# Fuente_Alimentaci_n.net
KiCad netlist of a schematic drawn in EAGLE
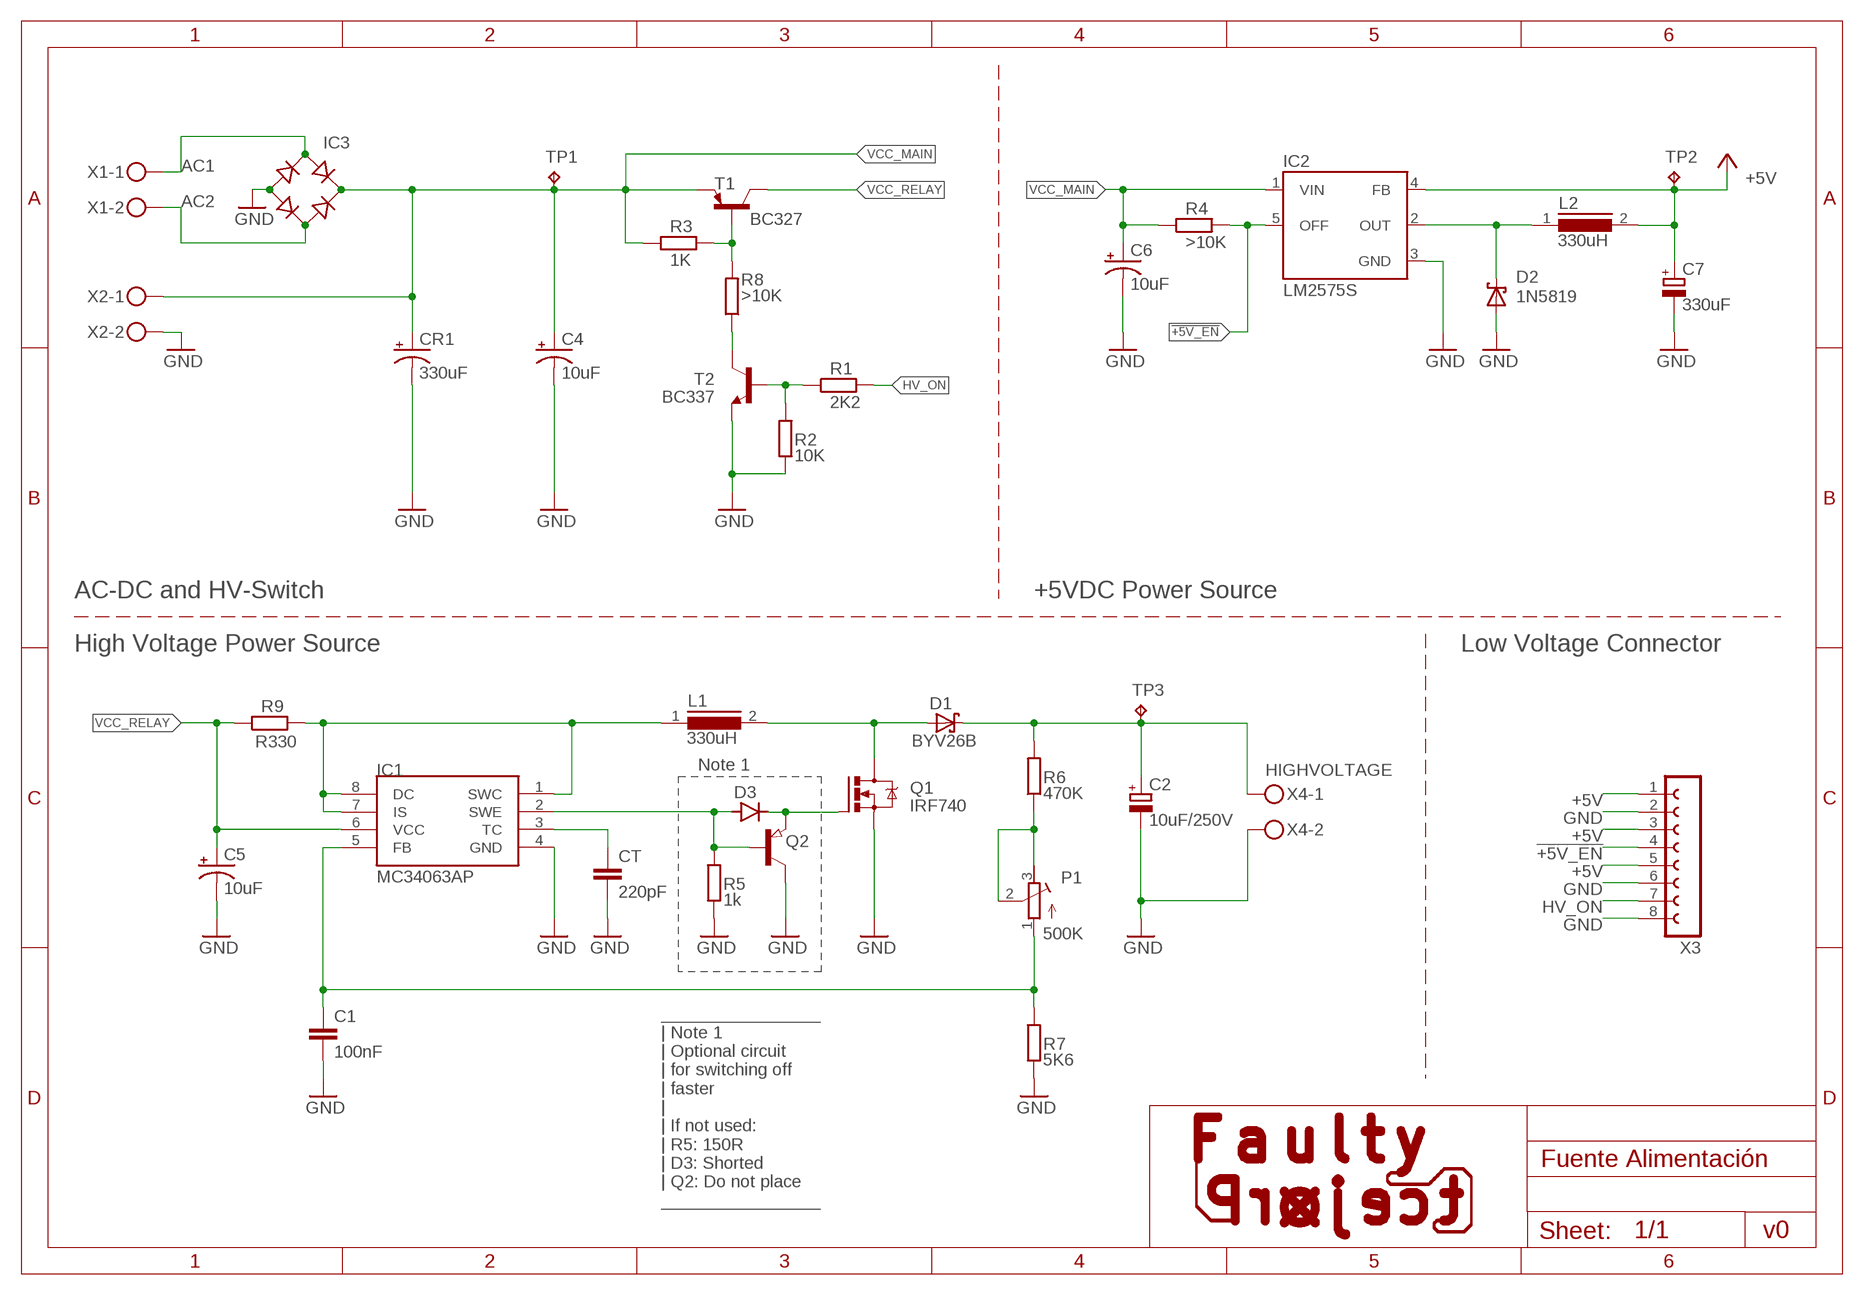
[diagram p0: schematic, sheet 1]

(export (version "E")
  (design (tool "Eeschema 10.0.6"))
  (components
    (comp (ref "C1")
      (value "100nF")
      (footprint "eagle-import:C1808")
      (libsource (lib "eagle-import") (part "C-EUC1808"))
    )
    (comp (ref "C2")
      (value "10uF/250V")
      (footprint "eagle-import:E5-13")
      (libsource (lib "eagle-import") (part "CPOL-EUE5-13"))
    )
    (comp (ref "C4")
      (value "10uF")
      (footprint "eagle-import:085CS_1AR")
      (libsource (lib "eagle-import") (part "CPOL-US085CS-1AR"))
    )
    (comp (ref "C5")
      (value "10uF")
      (footprint "eagle-import:085CS_1AR")
      (libsource (lib "eagle-import") (part "CPOL-US085CS-1AR"))
    )
    (comp (ref "C6")
      (value "10uF")
      (footprint "eagle-import:085CS_1AR")
      (libsource (lib "eagle-import") (part "CPOL-US085CS-1AR"))
    )
    (comp (ref "C7")
      (value "330uF")
      (footprint "eagle-import:E5-10,5")
      (libsource (lib "eagle-import") (part "CPOL-EUE5-10.5"))
    )
    (comp (ref "CR1")
      (value "330uF")
      (footprint "eagle-import:E5-13")
      (libsource (lib "eagle-import") (part "CPOL-USE5-13"))
    )
    (comp (ref "CT")
      (value "220pF")
      (footprint "eagle-import:C025-024X044")
      (libsource (lib "eagle-import") (part "C-EU025-024X044"))
    )
    (comp (ref "D1")
      (value "BYV26B")
      (footprint "eagle-import:DO41-7.6")
      (libsource (lib "eagle-import") (part "1N5817-B"))
    )
    (comp (ref "D2")
      (value "1N5819")
      (footprint "eagle-import:DO41-7.6")
      (libsource (lib "eagle-import") (part "1N5819-T"))
    )
    (comp (ref "D3")
      (value "MBR0520LT")
      (footprint "eagle-import:SOD123")
      (libsource (lib "eagle-import") (part "MBR0520LT"))
    )
    (comp (ref "IC1")
      (value "MC34063AP")
      (footprint "eagle-import:DIL08")
      (libsource (lib "eagle-import") (part "MC34063AP"))
    )
    (comp (ref "IC2")
      (value "LM2575S")
      (footprint "eagle-import:TO263-5")
      (libsource (lib "eagle-import") (part "LM2575S"))
    )
    (comp (ref "IC3")
      (value "B-DIL")
      (footprint "eagle-import:B-DIL")
      (libsource (lib "eagle-import") (part "B-DIL"))
    )
    (comp (ref "L1")
      (value "330uH")
      (footprint "eagle-import:DR125")
      (libsource (lib "eagle-import") (part "DR125"))
    )
    (comp (ref "L2")
      (value "330uH")
      (footprint "eagle-import:DR125")
      (libsource (lib "eagle-import") (part "DR125"))
    )
    (comp (ref "P1")
      (value "500K")
      (footprint "eagle-import:RTRIM64W")
      (libsource (lib "eagle-import") (part "R-TRIMM64W"))
    )
    (comp (ref "Q1")
      (value "IRF740")
      (footprint "eagle-import:TO220BV")
      (libsource (lib "eagle-import") (part "IRF740"))
    )
    (comp (ref "Q2")
      (value "PNP-TRANSISTOR_SOT23")
      (footprint "eagle-import:SOT23")
      (libsource (lib "eagle-import") (part "PNP-TRANSISTOR_SOT23"))
    )
    (comp (ref "R1")
      (value "2K2")
      (footprint "eagle-import:0207_2V")
      (libsource (lib "eagle-import") (part "R-EU_0207/2V"))
    )
    (comp (ref "R2")
      (value "10K")
      (footprint "eagle-import:0207_2V")
      (libsource (lib "eagle-import") (part "R-EU_0207/2V"))
    )
    (comp (ref "R3")
      (value "1K")
      (footprint "eagle-import:0204_5")
      (libsource (lib "eagle-import") (part "R-EU_0204/5"))
    )
    (comp (ref "R4")
      (value ">10K")
      (footprint "eagle-import:0207_2V")
      (libsource (lib "eagle-import") (part "R-EU_0207/2V"))
    )
    (comp (ref "R5")
      (value "1k")
      (footprint "eagle-import:0204V")
      (libsource (lib "eagle-import") (part "R-EU_0204/2V"))
    )
    (comp (ref "R6")
      (value "470K")
      (footprint "eagle-import:0204_7")
      (libsource (lib "eagle-import") (part "R-EU_0204/7"))
    )
    (comp (ref "R7")
      (value "5K6")
      (footprint "eagle-import:0204V")
      (libsource (lib "eagle-import") (part "R-EU_0204/2V"))
    )
    (comp (ref "R8")
      (value ">10K")
      (footprint "eagle-import:0204V")
      (libsource (lib "eagle-import") (part "R-EU_0204/2V"))
    )
    (comp (ref "R9")
      (value "R330")
      (footprint "eagle-import:0204V")
      (libsource (lib "eagle-import") (part "R-EU_0204/2V"))
    )
    (comp (ref "T1")
      (value "BC327")
      (footprint "eagle-import:TO92")
      (libsource (lib "eagle-import") (part "BC327"))
    )
    (comp (ref "T2")
      (value "BC337")
      (footprint "eagle-import:TO92")
      (libsource (lib "eagle-import") (part "BC337"))
    )
    (comp (ref "TP1")
      (value "TPB1,27")
      (footprint "eagle-import:B1,27")
      (libsource (lib "eagle-import") (part "TPB1,27"))
    )
    (comp (ref "TP2")
      (value "TPB1,27")
      (footprint "eagle-import:B1,27")
      (libsource (lib "eagle-import") (part "TPB1,27"))
    )
    (comp (ref "TP3")
      (value "TPB1,27")
      (footprint "eagle-import:B1,27")
      (libsource (lib "eagle-import") (part "TPB1,27"))
    )
    (comp (ref "X1")
      (value "MKDSN1,5/2-5,08")
      (footprint "eagle-import:MKDSN1,5_2-5,08")
      (libsource (lib "eagle-import") (part "MKDSN1,5/2-5,08"))
    )
    (comp (ref "X2")
      (value "MKDSN1,5/2-5,08")
      (footprint "eagle-import:MKDSN1,5_2-5,08")
      (libsource (lib "eagle-import") (part "MKDSN1,5/2-5,08"))
    )
    (comp (ref "X3")
      (value "FE08W")
      (footprint "eagle-import:FE08W")
      (libsource (lib "eagle-import") (part "FE08W"))
    )
    (comp (ref "X4")
      (value "MKDSN1,5/2-5,08")
      (footprint "eagle-import:MKDSN1,5_2-5,08")
      (libsource (lib "eagle-import") (part "MKDSN1,5/2-5,08"))
    )
  )
  (nets
    (net (code "1") (name "+5V") (class "Default")
      (node (ref "C7") (pin "+") (pinfunction "+_+") (pintype "passive"))
      (node (ref "IC2") (pin "4") (pinfunction "FB_4") (pintype "input"))
      (node (ref "L2") (pin "2") (pinfunction "2_2") (pintype "passive"))
      (node (ref "TP2") (pin "TP") (pinfunction "TP_TP") (pintype "input"))
      (node (ref "X3") (pin "1") (pinfunction "1_1") (pintype "passive"))
      (node (ref "X3") (pin "3") (pinfunction "3_3") (pintype "passive"))
      (node (ref "X3") (pin "5") (pinfunction "5_5") (pintype "passive"))
    )
    (net (code "2") (name "/AC1") (class "Default")
      (node (ref "IC3") (pin "AC2") (pinfunction "AC2_AC2") (pintype "passive"))
      (node (ref "X1") (pin "1") (pinfunction "KL_1") (pintype "passive"))
    )
    (net (code "3") (name "/AC2") (class "Default")
      (node (ref "IC3") (pin "AC1") (pinfunction "AC1_AC1") (pintype "passive"))
      (node (ref "X1") (pin "2") (pinfunction "KL_2") (pintype "passive"))
    )
    (net (code "4") (name "/HIGHVOLTAGE") (class "Default")
      (node (ref "C2") (pin "+") (pinfunction "+_+") (pintype "passive"))
      (node (ref "D1") (pin "C") (pinfunction "C_C") (pintype "passive"))
      (node (ref "R6") (pin "2") (pinfunction "2_2") (pintype "passive"))
      (node (ref "TP3") (pin "TP") (pinfunction "TP_TP") (pintype "input"))
      (node (ref "X4") (pin "1") (pinfunction "KL_1") (pintype "passive"))
    )
    (net (code "5") (name "/~{+5V_EN}") (class "Default")
      (node (ref "IC2") (pin "5") (pinfunction "OFF_5") (pintype "input"))
      (node (ref "R4") (pin "2") (pinfunction "2_2") (pintype "passive"))
      (node (ref "X3") (pin "4") (pinfunction "4_4") (pintype "passive"))
    )
    (net (code "6") (name "GND") (class "Default")
      (node (ref "C1") (pin "2") (pinfunction "2_2") (pintype "passive"))
      (node (ref "C2") (pin "-") (pinfunction "-_-") (pintype "passive"))
      (node (ref "C4") (pin "-") (pinfunction "-_-") (pintype "passive"))
      (node (ref "C5") (pin "-") (pinfunction "-_-") (pintype "passive"))
      (node (ref "C6") (pin "-") (pinfunction "-_-") (pintype "passive"))
      (node (ref "C7") (pin "-") (pinfunction "-_-") (pintype "passive"))
      (node (ref "CR1") (pin "-") (pinfunction "-_-") (pintype "passive"))
      (node (ref "CT") (pin "2") (pinfunction "2_2") (pintype "passive"))
      (node (ref "D2") (pin "A") (pinfunction "A_A") (pintype "passive"))
      (node (ref "IC1") (pin "4") (pinfunction "GND_4") (pintype "passive"))
      (node (ref "IC2") (pin "3") (pinfunction "GND_3") (pintype "power_in"))
      (node (ref "IC3") (pin "-") (pinfunction "-_-") (pintype "passive"))
      (node (ref "Q1") (pin "S") (pinfunction "S_S") (pintype "passive"))
      (node (ref "Q2") (pin "3") (pinfunction "C_3") (pintype "passive"))
      (node (ref "R2") (pin "1") (pinfunction "1_1") (pintype "passive"))
      (node (ref "R5") (pin "1") (pinfunction "1_1") (pintype "passive"))
      (node (ref "R7") (pin "1") (pinfunction "1_1") (pintype "passive"))
      (node (ref "T2") (pin "1") (pinfunction "E_1") (pintype "passive"))
      (node (ref "X2") (pin "2") (pinfunction "KL_2") (pintype "passive"))
      (node (ref "X3") (pin "2") (pinfunction "2_2") (pintype "passive"))
      (node (ref "X3") (pin "6") (pinfunction "6_6") (pintype "passive"))
      (node (ref "X3") (pin "8") (pinfunction "8_8") (pintype "passive"))
      (node (ref "X4") (pin "2") (pinfunction "KL_2") (pintype "passive"))
    )
    (net (code "7") (name "HV_ON") (class "Default")
      (node (ref "R1") (pin "2") (pinfunction "2_2") (pintype "passive"))
      (node (ref "X3") (pin "7") (pinfunction "7_7") (pintype "passive"))
    )
    (net (code "8") (name "Net-(D1-PadA)") (class "Default")
      (node (ref "D1") (pin "A") (pinfunction "A_A") (pintype "passive"))
      (node (ref "L1") (pin "2") (pinfunction "2_2") (pintype "passive"))
      (node (ref "Q1") (pin "D") (pinfunction "D_D") (pintype "passive"))
    )
    (net (code "9") (name "Net-(IC1-DC)") (class "Default")
      (node (ref "IC1") (pin "1") (pinfunction "SWC_1") (pintype "passive"))
      (node (ref "IC1") (pin "7") (pinfunction "IS_7") (pintype "passive"))
      (node (ref "IC1") (pin "8") (pinfunction "DC_8") (pintype "passive"))
      (node (ref "L1") (pin "1") (pinfunction "1_1") (pintype "passive"))
      (node (ref "R9") (pin "2") (pinfunction "2_2") (pintype "passive"))
    )
    (net (code "10") (name "Net-(IC1-FB)") (class "Default")
      (node (ref "C1") (pin "1") (pinfunction "1_1") (pintype "passive"))
      (node (ref "IC1") (pin "5") (pinfunction "FB_5") (pintype "passive"))
      (node (ref "P1") (pin "1") (pinfunction "A_1") (pintype "passive"))
      (node (ref "R7") (pin "2") (pinfunction "2_2") (pintype "passive"))
    )
    (net (code "11") (name "Net-(IC1-SWE)") (class "Default")
      (node (ref "D3") (pin "A") (pinfunction "A_A") (pintype "passive"))
      (node (ref "IC1") (pin "2") (pinfunction "SWE_2") (pintype "passive"))
      (node (ref "Q2") (pin "1") (pinfunction "B_1") (pintype "passive"))
      (node (ref "R5") (pin "2") (pinfunction "2_2") (pintype "passive"))
    )
    (net (code "12") (name "Net-(IC1-TC)") (class "Default")
      (node (ref "CT") (pin "1") (pinfunction "1_1") (pintype "passive"))
      (node (ref "IC1") (pin "3") (pinfunction "TC_3") (pintype "passive"))
    )
    (net (code "13") (name "Net-(IC2-OUT)") (class "Default")
      (node (ref "D2") (pin "C") (pinfunction "C_C") (pintype "passive"))
      (node (ref "IC2") (pin "2") (pinfunction "OUT_2") (pintype "output"))
      (node (ref "L2") (pin "1") (pinfunction "1_1") (pintype "passive"))
    )
    (net (code "14") (name "Net-(P1-E)") (class "Default")
      (node (ref "P1") (pin "2") (pinfunction "S_2") (pintype "passive"))
      (node (ref "P1") (pin "3") (pinfunction "E_3") (pintype "passive"))
      (node (ref "R6") (pin "1") (pinfunction "1_1") (pintype "passive"))
    )
    (net (code "15") (name "Net-(Q2-E)") (class "Default")
      (node (ref "D3") (pin "C") (pinfunction "C_C") (pintype "passive"))
      (node (ref "Q1") (pin "G") (pinfunction "G_G") (pintype "passive"))
      (node (ref "Q2") (pin "2") (pinfunction "E_2") (pintype "passive"))
    )
    (net (code "16") (name "Net-(T1-B)") (class "Default")
      (node (ref "R3") (pin "2") (pinfunction "2_2") (pintype "passive"))
      (node (ref "R8") (pin "2") (pinfunction "2_2") (pintype "passive"))
      (node (ref "T1") (pin "2") (pinfunction "B_2") (pintype "passive"))
    )
    (net (code "17") (name "Net-(T2-B)") (class "Default")
      (node (ref "R1") (pin "1") (pinfunction "1_1") (pintype "passive"))
      (node (ref "R2") (pin "2") (pinfunction "2_2") (pintype "passive"))
      (node (ref "T2") (pin "2") (pinfunction "B_2") (pintype "passive"))
    )
    (net (code "18") (name "Net-(T2-C)") (class "Default")
      (node (ref "R8") (pin "1") (pinfunction "1_1") (pintype "passive"))
      (node (ref "T2") (pin "3") (pinfunction "C_3") (pintype "passive"))
    )
    (net (code "19") (name "VCC_MAIN") (class "Default")
      (node (ref "C4") (pin "+") (pinfunction "+_+") (pintype "passive"))
      (node (ref "C6") (pin "+") (pinfunction "+_+") (pintype "passive"))
      (node (ref "CR1") (pin "+") (pinfunction "+_+") (pintype "passive"))
      (node (ref "IC2") (pin "1") (pinfunction "VIN_1") (pintype "power_in"))
      (node (ref "IC3") (pin "+") (pinfunction "+_+") (pintype "passive"))
      (node (ref "R3") (pin "1") (pinfunction "1_1") (pintype "passive"))
      (node (ref "R4") (pin "1") (pinfunction "1_1") (pintype "passive"))
      (node (ref "T1") (pin "1") (pinfunction "E_1") (pintype "passive"))
      (node (ref "TP1") (pin "TP") (pinfunction "TP_TP") (pintype "input"))
      (node (ref "X2") (pin "1") (pinfunction "KL_1") (pintype "passive"))
    )
    (net (code "20") (name "VCC_RELAY") (class "Default")
      (node (ref "C5") (pin "+") (pinfunction "+_+") (pintype "passive"))
      (node (ref "IC1") (pin "6") (pinfunction "VCC_6") (pintype "passive"))
      (node (ref "R9") (pin "1") (pinfunction "1_1") (pintype "passive"))
      (node (ref "T1") (pin "3") (pinfunction "C_3") (pintype "passive"))
    )
  )
)
